# Logomatic.net
KiCad netlist of a schematic drawn in EAGLE
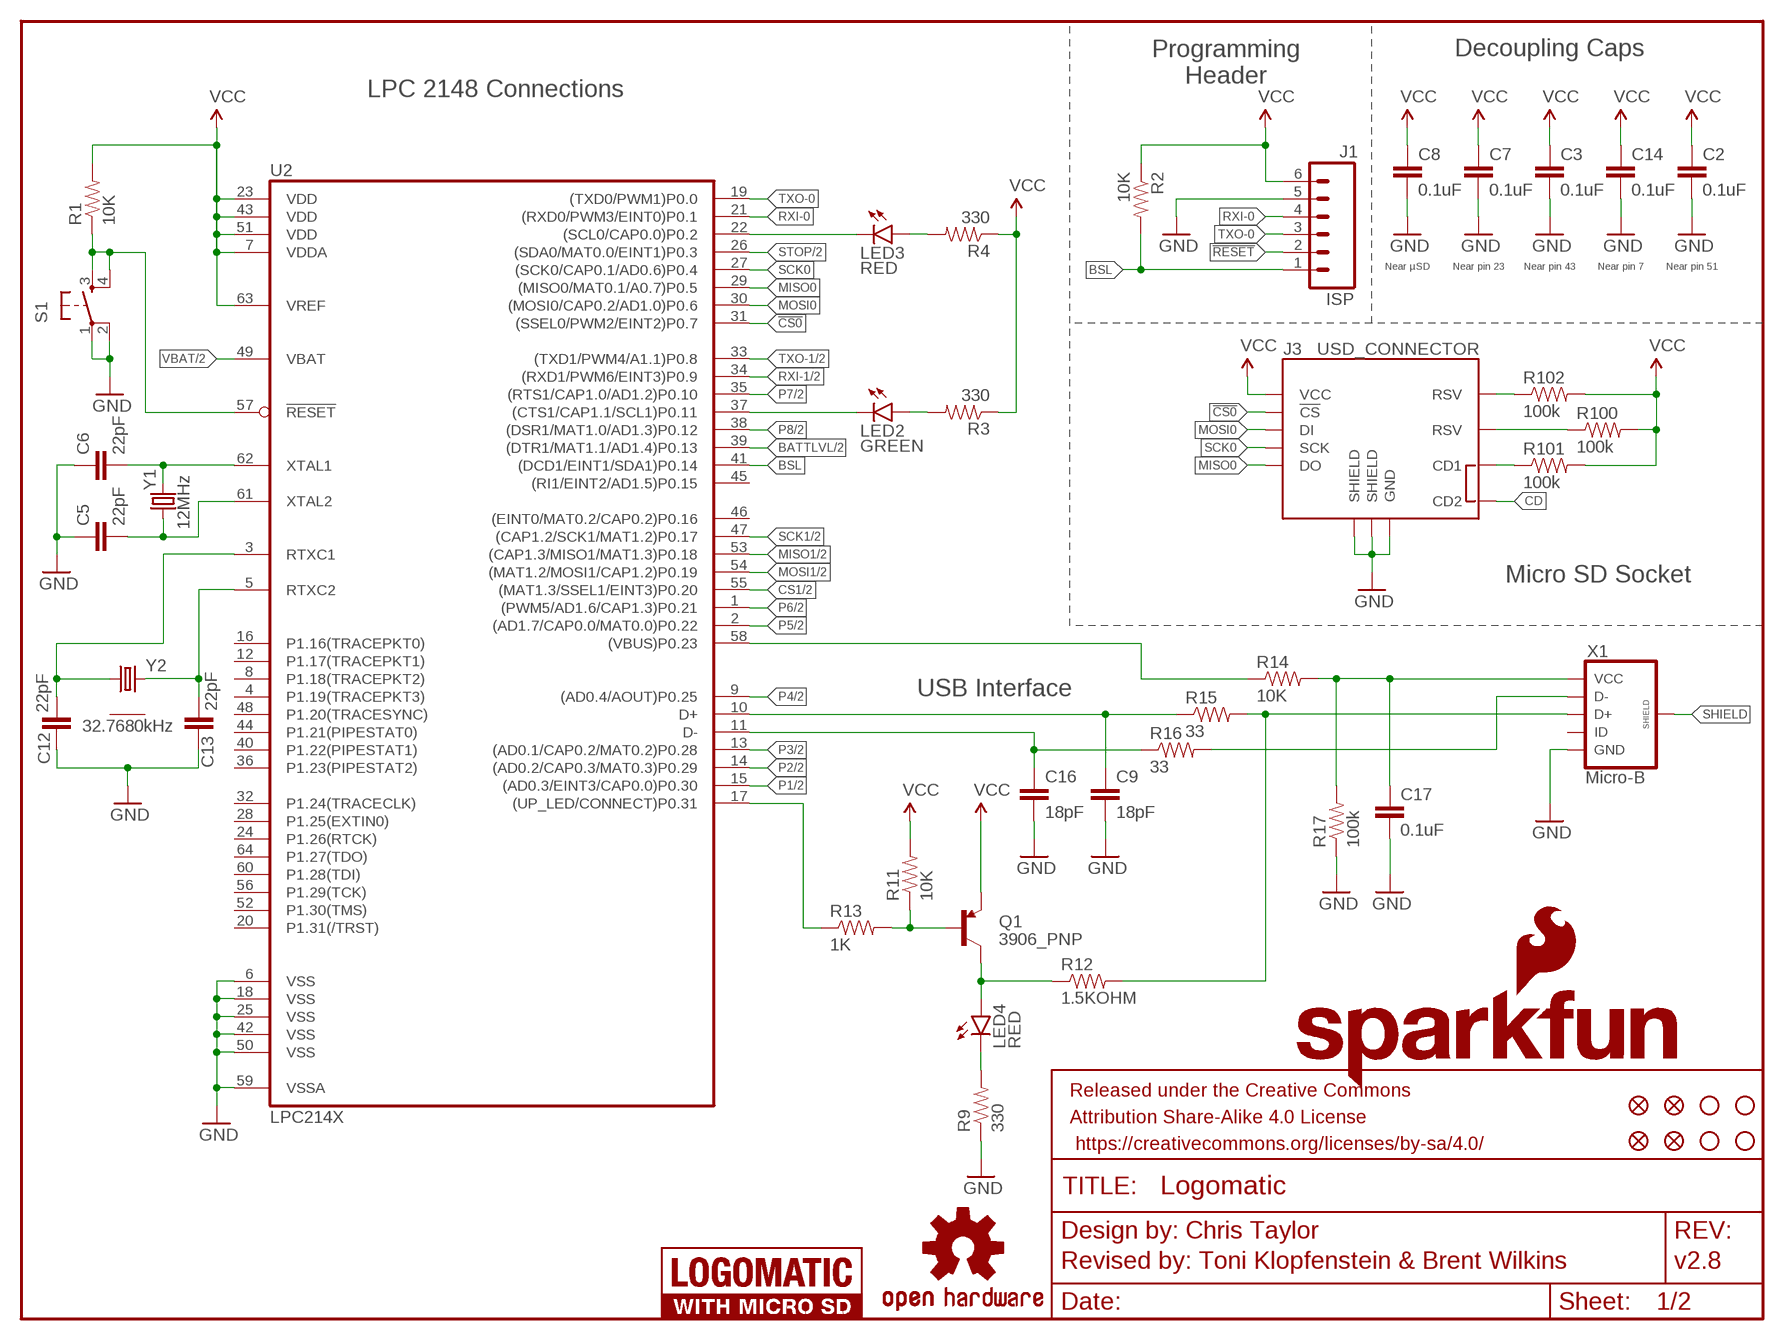
[diagram p0: schematic, sheet 1]
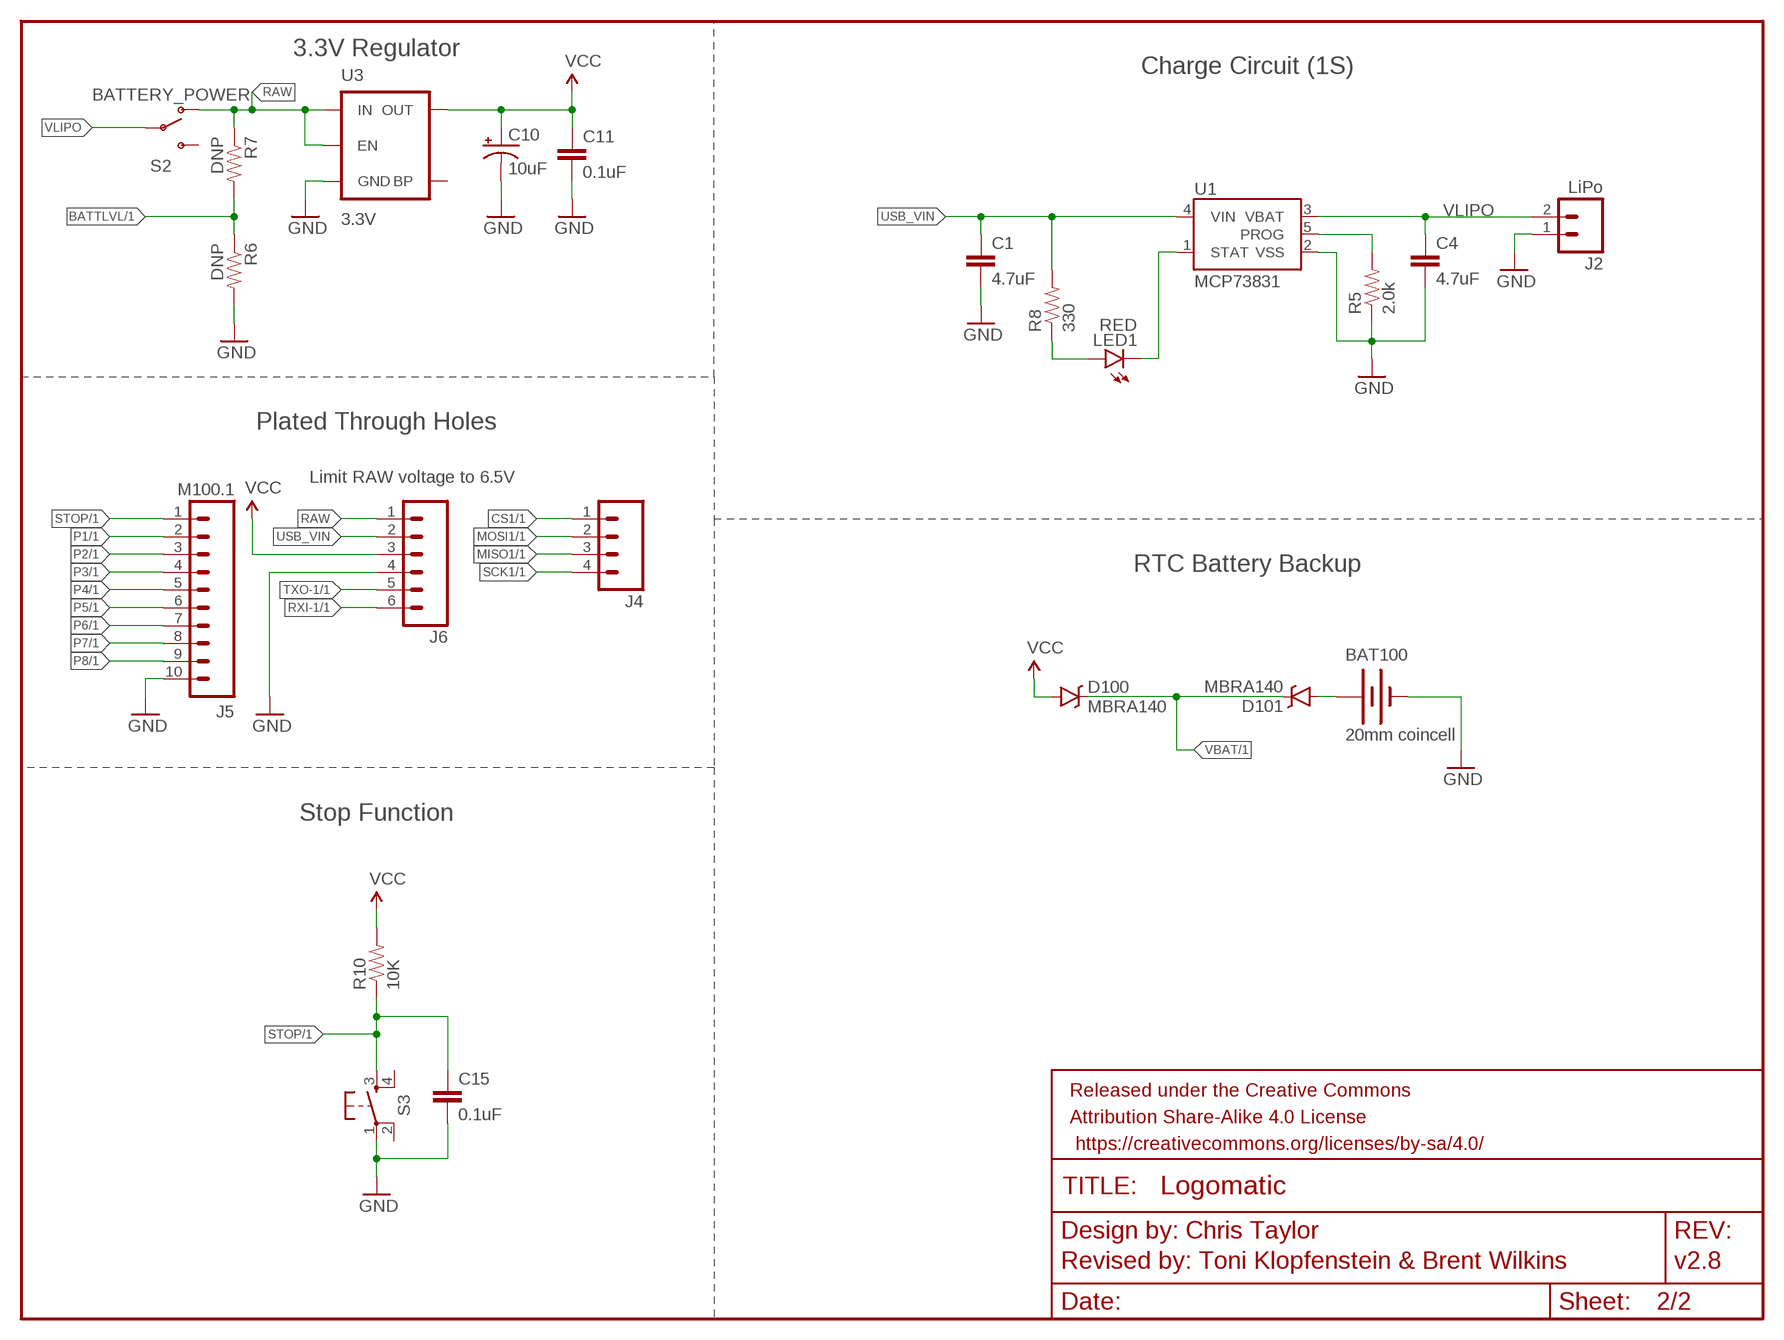
[diagram p1: schematic, sheet 2]

(export (version "E")
  (design (tool "Eeschema 10.0.6"))
  (components
    (comp (ref "BAT100")
      (value "20mm coincell")
      (footprint "eagle-import:BATTCON_20MM_4LEGS")
      (libsource (lib "eagle-import") (part "BATTERY20MM_4LEGS"))
    )
    (comp (ref "C1")
      (value "4.7uF")
      (footprint "eagle-import:0603-CAP")
      (libsource (lib "eagle-import") (part "4.7UF-6.3V-10%(0603)0603"))
    )
    (comp (ref "C4")
      (value "4.7uF")
      (footprint "eagle-import:0603-CAP")
      (libsource (lib "eagle-import") (part "4.7UF-6.3V-10%(0603)0603"))
    )
    (comp (ref "C10")
      (value "10uF")
      (footprint "eagle-import:EIA3216")
      (libsource (lib "eagle-import") (part "10UF-16V-10%(TANT)"))
    )
    (comp (ref "C11")
      (value "0.1uF")
      (footprint "eagle-import:0603-CAP")
      (libsource (lib "eagle-import") (part "0.1UF-25V(+80/-20%)(0603)"))
    )
    (comp (ref "C15")
      (value "0.1uF")
      (footprint "eagle-import:0603-CAP")
      (libsource (lib "eagle-import") (part "0.1UF-25V(+80/-20%)(0603)"))
    )
    (comp (ref "D100")
      (value "MBRA140")
      (footprint "eagle-import:SMA-DIODE")
      (libsource (lib "eagle-import") (part "MBRA140"))
    )
    (comp (ref "D101")
      (value "MBRA140")
      (footprint "eagle-import:SMA-DIODE")
      (libsource (lib "eagle-import") (part "MBRA140"))
    )
    (comp (ref "FRAME2")
      (value "FRAME-LETTERNO_PACKAGE")
      (footprint "eagle-import:DUMMY")
      (fields (field (name "DESIGNER") "Nobody"))
      (libsource (lib "eagle-import") (part "FRAME-LETTERNO_PACKAGE"))
    )
    (comp (ref "J2")
      (value "LiPo")
      (footprint "eagle-import:JST-2-SMD")
      (libsource (lib "eagle-import") (part "M02-JST-2MM-SMT"))
    )
    (comp (ref "J4")
      (value "M04PTH")
      (footprint "eagle-import:1X04")
      (libsource (lib "eagle-import") (part "M04PTH"))
    )
    (comp (ref "J5")
      (value "M100.1")
      (footprint "eagle-import:1X10")
      (libsource (lib "eagle-import") (part "M10SILK_FEMALE_PTH"))
    )
    (comp (ref "J6")
      (value "M06SILK_FEMALE_PTH")
      (footprint "eagle-import:1X06")
      (libsource (lib "eagle-import") (part "M06SILK_FEMALE_PTH"))
    )
    (comp (ref "LED1")
      (value "RED")
      (footprint "eagle-import:LED-0603")
      (libsource (lib "eagle-import") (part "LED-RED0603"))
    )
    (comp (ref "R5")
      (value "2.0k")
      (footprint "eagle-import:0603-RES")
      (libsource (lib "eagle-import") (part "2.0KOHM1/10W5%(0603)"))
    )
    (comp (ref "R6")
      (value "DNP")
      (footprint "eagle-import:0603-RES")
      (libsource (lib "eagle-import") (part "1MOHM-1/10W-1%(0603)"))
    )
    (comp (ref "R7")
      (value "DNP")
      (footprint "eagle-import:0603-RES")
      (libsource (lib "eagle-import") (part "1MOHM-1/10W-1%(0603)"))
    )
    (comp (ref "R8")
      (value "330")
      (footprint "eagle-import:0603-RES")
      (libsource (lib "eagle-import") (part "330OHM1/10W1%(0603)"))
    )
    (comp (ref "R10")
      (value "10K")
      (footprint "eagle-import:0603-RES")
      (libsource (lib "eagle-import") (part "10KOHM-1/10W-1%(0603)0603"))
    )
    (comp (ref "S2")
      (value "BATTERY_POWER")
      (footprint "eagle-import:AYZ0202")
      (libsource (lib "eagle-import") (part "SWITCH-SPDTSMD"))
    )
    (comp (ref "S3")
      (value "TAC_SWITCHSMD")
      (footprint "eagle-import:TACTILE-SWITCH-SMD")
      (libsource (lib "eagle-import") (part "TAC_SWITCHSMD"))
    )
    (comp (ref "U1")
      (value "MCP73831")
      (footprint "eagle-import:SOT23-5")
      (libsource (lib "eagle-import") (part "MCP73831"))
    )
    (comp (ref "U3")
      (value "3.3V")
      (footprint "eagle-import:SOT23-5")
      (libsource (lib "eagle-import") (part "MIC52053.3V"))
    )
    (comp (ref "C2")
      (value "0.1uF")
      (footprint "eagle-import:0603-CAP")
      (libsource (lib "eagle-import") (part "0.1UF-25V(+80/-20%)(0603)"))
    )
    (comp (ref "C3")
      (value "0.1uF")
      (footprint "eagle-import:0603-CAP")
      (libsource (lib "eagle-import") (part "0.1UF-25V(+80/-20%)(0603)"))
    )
    (comp (ref "C5")
      (value "22pF")
      (footprint "eagle-import:0603-CAP")
      (libsource (lib "eagle-import") (part "22PF-50V-5%(0603)"))
    )
    (comp (ref "C6")
      (value "22pF")
      (footprint "eagle-import:0603-CAP")
      (libsource (lib "eagle-import") (part "22PF-50V-5%(0603)"))
    )
    (comp (ref "C7")
      (value "0.1uF")
      (footprint "eagle-import:0603-CAP")
      (libsource (lib "eagle-import") (part "0.1UF-25V(+80/-20%)(0603)"))
    )
    (comp (ref "C8")
      (value "0.1uF")
      (footprint "eagle-import:0603-CAP")
      (libsource (lib "eagle-import") (part "0.1UF-25V(+80/-20%)(0603)"))
    )
    (comp (ref "C9")
      (value "18pF")
      (footprint "eagle-import:0603-CAP")
      (libsource (lib "eagle-import") (part "18PF-50V-5%(0603)"))
    )
    (comp (ref "C12")
      (value "22pF")
      (footprint "eagle-import:0603-CAP")
      (libsource (lib "eagle-import") (part "22PF-50V-5%(0603)"))
    )
    (comp (ref "C13")
      (value "22pF")
      (footprint "eagle-import:0603-CAP")
      (libsource (lib "eagle-import") (part "22PF-50V-5%(0603)"))
    )
    (comp (ref "C14")
      (value "0.1uF")
      (footprint "eagle-import:0603-CAP")
      (libsource (lib "eagle-import") (part "0.1UF-25V(+80/-20%)(0603)"))
    )
    (comp (ref "C16")
      (value "18pF")
      (footprint "eagle-import:0603-CAP")
      (libsource (lib "eagle-import") (part "18PF-50V-5%(0603)"))
    )
    (comp (ref "C17")
      (value "0.1uF")
      (footprint "eagle-import:0603-CAP")
      (libsource (lib "eagle-import") (part "0.1UF-25V(+80/-20%)(0603)"))
    )
    (comp (ref "FD1")
      (value "FIDUCIAL1X2")
      (footprint "eagle-import:FIDUCIAL-1X2")
      (libsource (lib "eagle-import") (part "FIDUCIAL1X2"))
    )
    (comp (ref "FD2")
      (value "FIDUCIAL1X2")
      (footprint "eagle-import:FIDUCIAL-1X2")
      (libsource (lib "eagle-import") (part "FIDUCIAL1X2"))
    )
    (comp (ref "FD100")
      (value "FIDUCIAL1X2")
      (footprint "eagle-import:FIDUCIAL-1X2")
      (libsource (lib "eagle-import") (part "FIDUCIAL1X2"))
    )
    (comp (ref "FD101")
      (value "FIDUCIAL1X2")
      (footprint "eagle-import:FIDUCIAL-1X2")
      (libsource (lib "eagle-import") (part "FIDUCIAL1X2"))
    )
    (comp (ref "FRAME1")
      (value "FRAME-LETTER")
      (footprint "eagle-import:CREATIVE_COMMONS")
      (libsource (lib "eagle-import") (part "FRAME-LETTER"))
    )
    (comp (ref "H1")
      (value "STAND-OFF")
      (footprint "eagle-import:STAND-OFF")
      (libsource (lib "eagle-import") (part "STAND-OFF"))
    )
    (comp (ref "H2")
      (value "STAND-OFF")
      (footprint "eagle-import:STAND-OFF")
      (libsource (lib "eagle-import") (part "STAND-OFF"))
    )
    (comp (ref "H3")
      (value "STAND-OFF")
      (footprint "eagle-import:STAND-OFF")
      (libsource (lib "eagle-import") (part "STAND-OFF"))
    )
    (comp (ref "H4")
      (value "STAND-OFF")
      (footprint "eagle-import:STAND-OFF")
      (libsource (lib "eagle-import") (part "STAND-OFF"))
    )
    (comp (ref "J1")
      (value "ISP")
      (footprint "eagle-import:1X06")
      (libsource (lib "eagle-import") (part "M06SILK_FEMALE_PTH"))
    )
    (comp (ref "J3")
      (value "USD_CONNECTOR")
      (footprint "eagle-import:MICRO-SD-SOCKET-PP")
      (libsource (lib "eagle-import") (part "USD_CONNECTOR"))
    )
    (comp (ref "LED2")
      (value "GREEN")
      (footprint "eagle-import:LED-0603")
      (libsource (lib "eagle-import") (part "LED-GREEN0603"))
    )
    (comp (ref "LED3")
      (value "RED")
      (footprint "eagle-import:LED-0603")
      (libsource (lib "eagle-import") (part "LED-RED0603"))
    )
    (comp (ref "LED4")
      (value "RED")
      (footprint "eagle-import:LED-0603")
      (libsource (lib "eagle-import") (part "LED-RED0603"))
    )
    (comp (ref "LOGO1")
      (value "SFE_LOGO_NAME.1_INCH")
      (footprint "eagle-import:SFE_LOGO_NAME_.1")
      (libsource (lib "eagle-import") (part "SFE_LOGO_NAME.1_INCH"))
    )
    (comp (ref "LOGO2")
      (value "SFE_LOGO_FLAME.1_INCH")
      (footprint "eagle-import:SFE_LOGO_FLAME_.1")
      (libsource (lib "eagle-import") (part "SFE_LOGO_FLAME.1_INCH"))
    )
    (comp (ref "LOGO100")
      (value "OSHW-LOGOL")
      (footprint "eagle-import:OSHW-LOGO-L")
      (libsource (lib "eagle-import") (part "OSHW-LOGOL"))
    )
    (comp (ref "LOGO101")
      (value "LOGOMATIC_LOGO")
      (footprint "eagle-import:LOGOMATIC_LOGO")
      (libsource (lib "eagle-import") (part "LOGOMATIC_LOGO"))
    )
    (comp (ref "Q1")
      (value "3906_PNP")
      (footprint "eagle-import:SOT23-3")
      (libsource (lib "eagle-import") (part "TRANSISTOR_PNPPMBT3906"))
    )
    (comp (ref "R1")
      (value "10K")
      (footprint "eagle-import:0603-RES")
      (libsource (lib "eagle-import") (part "10KOHM-1/10W-1%(0603)0603"))
    )
    (comp (ref "R2")
      (value "10K")
      (footprint "eagle-import:0603-RES")
      (libsource (lib "eagle-import") (part "10KOHM-1/10W-1%(0603)0603"))
    )
    (comp (ref "R3")
      (value "330")
      (footprint "eagle-import:0603-RES")
      (libsource (lib "eagle-import") (part "330OHM1/10W1%(0603)"))
    )
    (comp (ref "R4")
      (value "330")
      (footprint "eagle-import:0603-RES")
      (libsource (lib "eagle-import") (part "330OHM1/10W1%(0603)"))
    )
    (comp (ref "R9")
      (value "330")
      (footprint "eagle-import:0603-RES")
      (libsource (lib "eagle-import") (part "330OHM1/10W1%(0603)"))
    )
    (comp (ref "R11")
      (value "10K")
      (footprint "eagle-import:0603-RES")
      (libsource (lib "eagle-import") (part "10KOHM-1/10W-1%(0603)0603"))
    )
    (comp (ref "R12")
      (value "1.5KOHM")
      (footprint "eagle-import:0603")
      (libsource (lib "eagle-import") (part "1.5KOHM-1/10W-1%(0603)"))
    )
    (comp (ref "R13")
      (value "1K")
      (footprint "eagle-import:0603-RES")
      (libsource (lib "eagle-import") (part "1KOHM-1/10W-1%(0603)"))
    )
    (comp (ref "R14")
      (value "10K")
      (footprint "eagle-import:0603-RES")
      (libsource (lib "eagle-import") (part "10KOHM-1/10W-1%(0603)0603"))
    )
    (comp (ref "R15")
      (value "33")
      (footprint "eagle-import:0603-RES")
      (libsource (lib "eagle-import") (part "33OHM1/10W1%(0603)"))
    )
    (comp (ref "R16")
      (value "33")
      (footprint "eagle-import:0603-RES")
      (libsource (lib "eagle-import") (part "33OHM1/10W1%(0603)"))
    )
    (comp (ref "R17")
      (value "100k")
      (footprint "eagle-import:0603-RES")
      (libsource (lib "eagle-import") (part "100KOHM-1/10W-1%(0603)"))
    )
    (comp (ref "R100")
      (value "100k")
      (footprint "eagle-import:0603-RES")
      (libsource (lib "eagle-import") (part "100KOHM-1/10W-1%(0603)"))
    )
    (comp (ref "R101")
      (value "100k")
      (footprint "eagle-import:0603-RES")
      (libsource (lib "eagle-import") (part "100KOHM-1/10W-1%(0603)"))
    )
    (comp (ref "R102")
      (value "100k")
      (footprint "eagle-import:0603-RES")
      (libsource (lib "eagle-import") (part "100KOHM-1/10W-1%(0603)"))
    )
    (comp (ref "S1")
      (value "RESET")
      (footprint "eagle-import:TACTILE-SWITCH-SMD")
      (libsource (lib "eagle-import") (part "TAC_SWITCHSMD"))
    )
    (comp (ref "U2")
      (value "LPC214X")
      (footprint "eagle-import:LQFP-10X10-64")
      (libsource (lib "eagle-import") (part "LPC214X"))
    )
    (comp (ref "X1")
      (value "Micro-B")
      (footprint "eagle-import:USB-B-MICRO-SMD_V03")
      (libsource (lib "eagle-import") (part "USB_MICROB_PLUGCONN-11752"))
    )
    (comp (ref "Y1")
      (value "12MHz")
      (footprint "eagle-import:CRYSTAL-SMD-5X3")
      (libsource (lib "eagle-import") (part "CRYSTALCRYSTAL-SMD-5X3-12MHZ"))
    )
    (comp (ref "Y2")
      (value "32.7680kHz")
      (footprint "eagle-import:4-SOJ_5.5MM")
      (libsource (lib "eagle-import") (part "RTC_CRYSTAL32-SMD"))
    )
  )
  (nets
    (net (code "1") (name "BATTLVL") (class "Default")
      (node (ref "R6") (pin "1") (pinfunction "1_1") (pintype "passive"))
      (node (ref "R7") (pin "2") (pinfunction "2_2") (pintype "passive"))
      (node (ref "U2") (pin "39") (pinfunction "(DTR1/MAT1.1/AD1.4)P0.13_39") (pintype "bidirectional"))
    )
    (net (code "2") (name "BSL") (class "Default")
      (node (ref "J1") (pin "1") (pinfunction "1_1") (pintype "passive"))
      (node (ref "R2") (pin "2") (pinfunction "2_2") (pintype "passive"))
      (node (ref "U2") (pin "41") (pinfunction "(DCD1/EINT1/SDA1)P0.14_41") (pintype "bidirectional"))
    )
    (net (code "3") (name "CD") (class "Default")
      (node (ref "J3") (pin "CD2") (pinfunction "CD2_CD2") (pintype "bidirectional"))
    )
    (net (code "4") (name "CS1") (class "Default")
      (node (ref "J4") (pin "1") (pinfunction "1_1") (pintype "passive"))
      (node (ref "U2") (pin "55") (pinfunction "(MAT1.3/SSEL1/EINT3)P0.20_55") (pintype "bidirectional"))
    )
    (net (code "5") (name "GND") (class "Default")
      (node (ref "BAT100") (pin "NEGATIVE") (pinfunction "-_NEGATIVE") (pintype "power_in"))
      (node (ref "C1") (pin "2") (pinfunction "2_2") (pintype "passive"))
      (node (ref "C10") (pin "C") (pinfunction "-_C") (pintype "passive"))
      (node (ref "C11") (pin "2") (pinfunction "2_2") (pintype "passive"))
      (node (ref "C12") (pin "1") (pinfunction "1_1") (pintype "passive"))
      (node (ref "C13") (pin "1") (pinfunction "1_1") (pintype "passive"))
      (node (ref "C14") (pin "2") (pinfunction "2_2") (pintype "passive"))
      (node (ref "C15") (pin "2") (pinfunction "2_2") (pintype "passive"))
      (node (ref "C16") (pin "2") (pinfunction "2_2") (pintype "passive"))
      (node (ref "C17") (pin "2") (pinfunction "2_2") (pintype "passive"))
      (node (ref "C2") (pin "2") (pinfunction "2_2") (pintype "passive"))
      (node (ref "C3") (pin "2") (pinfunction "2_2") (pintype "passive"))
      (node (ref "C4") (pin "2") (pinfunction "2_2") (pintype "passive"))
      (node (ref "C5") (pin "1") (pinfunction "1_1") (pintype "passive"))
      (node (ref "C6") (pin "1") (pinfunction "1_1") (pintype "passive"))
      (node (ref "C7") (pin "2") (pinfunction "2_2") (pintype "passive"))
      (node (ref "C8") (pin "2") (pinfunction "2_2") (pintype "passive"))
      (node (ref "C9") (pin "2") (pinfunction "2_2") (pintype "passive"))
      (node (ref "J1") (pin "5") (pinfunction "5_5") (pintype "passive"))
      (node (ref "J2") (pin "1") (pinfunction "2_1") (pintype "passive"))
      (node (ref "J3") (pin "GND") (pinfunction "GND_GND") (pintype "bidirectional"))
      (node (ref "J3") (pin "GND1") (pinfunction "SHIELD_GND1") (pintype "bidirectional"))
      (node (ref "J3") (pin "GND3") (pinfunction "SHIELD_GND3") (pintype "bidirectional"))
      (node (ref "J5") (pin "10") (pinfunction "10_10") (pintype "passive"))
      (node (ref "J6") (pin "4") (pinfunction "4_4") (pintype "passive"))
      (node (ref "R17") (pin "1") (pinfunction "1_1") (pintype "passive"))
      (node (ref "R5") (pin "1") (pinfunction "1_1") (pintype "passive"))
      (node (ref "R6") (pin "2") (pinfunction "2_2") (pintype "passive"))
      (node (ref "R9") (pin "1") (pinfunction "1_1") (pintype "passive"))
      (node (ref "S1") (pin "1") (pinfunction "1_1") (pintype "passive"))
      (node (ref "S1") (pin "2") (pinfunction "2_2") (pintype "passive"))
      (node (ref "S3") (pin "1") (pinfunction "1_1") (pintype "passive"))
      (node (ref "U1") (pin "2") (pinfunction "VSS_2") (pintype "power_in"))
      (node (ref "U2") (pin "18") (pinfunction "VSS_18") (pintype "power_in"))
      (node (ref "U2") (pin "25") (pinfunction "VSS_25") (pintype "power_in"))
      (node (ref "U2") (pin "42") (pinfunction "VSS_42") (pintype "power_in"))
      (node (ref "U2") (pin "50") (pinfunction "VSS_50") (pintype "power_in"))
      (node (ref "U2") (pin "59") (pinfunction "VSSA_59") (pintype "power_in"))
      (node (ref "U2") (pin "6") (pinfunction "VSS_6") (pintype "power_in"))
      (node (ref "U3") (pin "2") (pinfunction "GND_2") (pintype "input"))
      (node (ref "X1") (pin "GND") (pinfunction "GND_GND") (pintype "bidirectional"))
    )
    (net (code "6") (name "MISO0") (class "Default")
      (node (ref "J3") (pin "DO") (pinfunction "DO_DO") (pintype "bidirectional"))
      (node (ref "U2") (pin "29") (pinfunction "(MISO0/MAT0.1/A0.7)P0.5_29") (pintype "bidirectional"))
    )
    (net (code "7") (name "MISO1") (class "Default")
      (node (ref "J4") (pin "3") (pinfunction "3_3") (pintype "passive"))
      (node (ref "U2") (pin "53") (pinfunction "(CAP1.3/MISO1/MAT1.3)P0.18_53") (pintype "bidirectional"))
    )
    (net (code "8") (name "MOSI0") (class "Default")
      (node (ref "J3") (pin "DI") (pinfunction "DI_DI") (pintype "bidirectional"))
      (node (ref "U2") (pin "30") (pinfunction "(MOSI0/CAP0.2/AD1.0)P0.6_30") (pintype "bidirectional"))
    )
    (net (code "9") (name "MOSI1") (class "Default")
      (node (ref "J4") (pin "2") (pinfunction "2_2") (pintype "passive"))
      (node (ref "U2") (pin "54") (pinfunction "(MAT1.2/MOSI1/CAP1.2)P0.19_54") (pintype "bidirectional"))
    )
    (net (code "10") (name "Net-(BAT100-+-PadPOSITIVE@1)") (class "Default")
      (node (ref "BAT100") (pin "POSITIVE@1") (pinfunction "+_POSITIVE@1") (pintype "power_in"))
      (node (ref "BAT100") (pin "POSITIVE@2") (pinfunction "+_POSITIVE@2") (pintype "power_in"))
      (node (ref "BAT100") (pin "POSITIVE@3") (pinfunction "+_POSITIVE@3") (pintype "power_in"))
      (node (ref "BAT100") (pin "POSITIVE@4") (pinfunction "+_POSITIVE@4") (pintype "power_in"))
      (node (ref "D101") (pin "A") (pinfunction "A_A") (pintype "passive"))
    )
    (net (code "11") (name "Net-(J3-PadCD1)") (class "Default")
      (node (ref "J3") (pin "CD1") (pinfunction "CD1_CD1") (pintype "bidirectional"))
      (node (ref "R101") (pin "1") (pinfunction "1_1") (pintype "passive"))
    )
    (net (code "12") (name "Net-(J3-RSV-PadRSV1)") (class "Default")
      (node (ref "J3") (pin "RSV1") (pinfunction "RSV_RSV1") (pintype "bidirectional"))
      (node (ref "R102") (pin "1") (pinfunction "1_1") (pintype "passive"))
    )
    (net (code "13") (name "Net-(J3-RSV-PadRSV2)") (class "Default")
      (node (ref "J3") (pin "RSV2") (pinfunction "RSV_RSV2") (pintype "bidirectional"))
      (node (ref "R100") (pin "1") (pinfunction "1_1") (pintype "passive"))
    )
    (net (code "14") (name "Net-(LED1-PadA)") (class "Default")
      (node (ref "LED1") (pin "A") (pinfunction "A_A") (pintype "passive"))
      (node (ref "R8") (pin "1") (pinfunction "1_1") (pintype "passive"))
    )
    (net (code "15") (name "Net-(LED2-PadA)") (class "Default")
      (node (ref "LED2") (pin "A") (pinfunction "A_A") (pintype "passive"))
      (node (ref "R3") (pin "2") (pinfunction "2_2") (pintype "passive"))
    )
    (net (code "16") (name "Net-(LED3-PadA)") (class "Default")
      (node (ref "LED3") (pin "A") (pinfunction "A_A") (pintype "passive"))
      (node (ref "R4") (pin "2") (pinfunction "2_2") (pintype "passive"))
    )
    (net (code "17") (name "Net-(LED4-PadC)") (class "Default")
      (node (ref "LED4") (pin "C") (pinfunction "C_C") (pintype "passive"))
      (node (ref "R9") (pin "2") (pinfunction "2_2") (pintype "passive"))
    )
    (net (code "18") (name "Net-(Q1-B)") (class "Default")
      (node (ref "Q1") (pin "1") (pinfunction "B_1") (pintype "passive"))
      (node (ref "R11") (pin "1") (pinfunction "1_1") (pintype "passive"))
      (node (ref "R13") (pin "2") (pinfunction "2_2") (pintype "passive"))
    )
    (net (code "19") (name "Net-(Q1-C)") (class "Default")
      (node (ref "LED4") (pin "A") (pinfunction "A_A") (pintype "passive"))
      (node (ref "Q1") (pin "3") (pinfunction "C_3") (pintype "passive"))
      (node (ref "R12") (pin "1") (pinfunction "1_1") (pintype "passive"))
    )
    (net (code "20") (name "Net-(R12-Pad2)") (class "Default")
      (node (ref "R12") (pin "2") (pinfunction "2_2") (pintype "passive"))
      (node (ref "R15") (pin "2") (pinfunction "2_2") (pintype "passive"))
      (node (ref "X1") (pin "D+") (pinfunction "D+_D+") (pintype "bidirectional"))
    )
    (net (code "21") (name "Net-(R16-Pad2)") (class "Default")
      (node (ref "R16") (pin "2") (pinfunction "2_2") (pintype "passive"))
      (node (ref "X1") (pin "D-") (pinfunction "D-_D-") (pintype "bidirectional"))
    )
    (net (code "22") (name "Net-(U1-PROG)") (class "Default")
      (node (ref "R5") (pin "2") (pinfunction "2_2") (pintype "passive"))
      (node (ref "U1") (pin "5") (pinfunction "PROG_5") (pintype "input"))
    )
    (net (code "23") (name "Net-(U1-STAT)") (class "Default")
      (node (ref "LED1") (pin "C") (pinfunction "C_C") (pintype "passive"))
      (node (ref "U1") (pin "1") (pinfunction "STAT_1") (pintype "output"))
    )
    (net (code "24") (name "Net-(U2-(CTS1{slash}CAP1.1{slash}SCL1)P0.11)") (class "Default")
      (node (ref "LED2") (pin "C") (pinfunction "C_C") (pintype "passive"))
      (node (ref "U2") (pin "37") (pinfunction "(CTS1/CAP1.1/SCL1)P0.11_37") (pintype "bidirectional"))
    )
    (net (code "25") (name "Net-(U2-(SCL0{slash}CAP0.0)P0.2)") (class "Default")
      (node (ref "LED3") (pin "C") (pinfunction "C_C") (pintype "passive"))
      (node (ref "U2") (pin "22") (pinfunction "(SCL0/CAP0.0)P0.2_22") (pintype "bidirectional"))
    )
    (net (code "26") (name "Net-(U2-(UP_LED{slash}CONNECT)P0.31)") (class "Default")
      (node (ref "R13") (pin "1") (pinfunction "1_1") (pintype "passive"))
      (node (ref "U2") (pin "17") (pinfunction "(UP_LED/CONNECT)P0.31_17") (pintype "bidirectional"))
    )
    (net (code "27") (name "Net-(U2-(VBUS)P0.23)") (class "Default")
      (node (ref "R14") (pin "1") (pinfunction "1_1") (pintype "passive"))
      (node (ref "U2") (pin "58") (pinfunction "(VBUS)P0.23_58") (pintype "bidirectional"))
    )
    (net (code "28") (name "Net-(U2-D+)") (class "Default")
      (node (ref "C9") (pin "1") (pinfunction "1_1") (pintype "passive"))
      (node (ref "R15") (pin "1") (pinfunction "1_1") (pintype "passive"))
      (node (ref "U2") (pin "10") (pinfunction "D+_10") (pintype "bidirectional"))
    )
    (net (code "29") (name "Net-(U2-D-)") (class "Default")
      (node (ref "C16") (pin "1") (pinfunction "1_1") (pintype "passive"))
      (node (ref "R16") (pin "1") (pinfunction "1_1") (pintype "passive"))
      (node (ref "U2") (pin "11") (pinfunction "D-_11") (pintype "bidirectional"))
    )
    (net (code "30") (name "Net-(U2-RTXC1)") (class "Default")
      (node (ref "C12") (pin "2") (pinfunction "2_2") (pintype "passive"))
      (node (ref "U2") (pin "3") (pinfunction "RTXC1_3") (pintype "input"))
      (node (ref "Y2") (pin "1") (pinfunction "1_1") (pintype "passive"))
    )
    (net (code "31") (name "Net-(U2-RTXC2)") (class "Default")
      (node (ref "C13") (pin "2") (pinfunction "2_2") (pintype "passive"))
      (node (ref "U2") (pin "5") (pinfunction "RTXC2_5") (pintype "output"))
      (node (ref "Y2") (pin "4") (pinfunction "4_4") (pintype "passive"))
    )
    (net (code "32") (name "Net-(U2-XTAL1)") (class "Default")
      (node (ref "C6") (pin "2") (pinfunction "2_2") (pintype "passive"))
      (node (ref "U2") (pin "62") (pinfunction "XTAL1_62") (pintype "input"))
      (node (ref "Y1") (pin "3") (pinfunction "2_3") (pintype "passive"))
    )
    (net (code "33") (name "Net-(U2-XTAL2)") (class "Default")
      (node (ref "C5") (pin "2") (pinfunction "2_2") (pintype "passive"))
      (node (ref "U2") (pin "61") (pinfunction "XTAL2_61") (pintype "output"))
      (node (ref "Y1") (pin "1") (pinfunction "1_1") (pintype "passive"))
    )
    (net (code "34") (name "P1") (class "Default")
      (node (ref "J5") (pin "2") (pinfunction "2_2") (pintype "passive"))
      (node (ref "U2") (pin "15") (pinfunction "(AD0.3/EINT3/CAP0.0)P0.30_15") (pintype "bidirectional"))
    )
    (net (code "35") (name "P2") (class "Default")
      (node (ref "J5") (pin "3") (pinfunction "3_3") (pintype "passive"))
      (node (ref "U2") (pin "14") (pinfunction "(AD0.2/CAP0.3/MAT0.3)P0.29_14") (pintype "bidirectional"))
    )
    (net (code "36") (name "P3") (class "Default")
      (node (ref "J5") (pin "4") (pinfunction "4_4") (pintype "passive"))
      (node (ref "U2") (pin "13") (pinfunction "(AD0.1/CAP0.2/MAT0.2)P0.28_13") (pintype "bidirectional"))
    )
    (net (code "37") (name "P4") (class "Default")
      (node (ref "J5") (pin "5") (pinfunction "5_5") (pintype "passive"))
      (node (ref "U2") (pin "9") (pinfunction "(AD0.4/AOUT)P0.25_9") (pintype "bidirectional"))
    )
    (net (code "38") (name "P5") (class "Default")
      (node (ref "J5") (pin "6") (pinfunction "6_6") (pintype "passive"))
      (node (ref "U2") (pin "2") (pinfunction "(AD1.7/CAP0.0/MAT0.0)P0.22_2") (pintype "bidirectional"))
    )
    (net (code "39") (name "P6") (class "Default")
      (node (ref "J5") (pin "7") (pinfunction "7_7") (pintype "passive"))
      (node (ref "U2") (pin "1") (pinfunction "(PWM5/AD1.6/CAP1.3)P0.21_1") (pintype "bidirectional"))
    )
    (net (code "40") (name "P7") (class "Default")
      (node (ref "J5") (pin "8") (pinfunction "8_8") (pintype "passive"))
      (node (ref "U2") (pin "35") (pinfunction "(RTS1/CAP1.0/AD1.2)P0.10_35") (pintype "bidirectional"))
    )
    (net (code "41") (name "P8") (class "Default")
      (node (ref "J5") (pin "9") (pinfunction "9_9") (pintype "passive"))
      (node (ref "U2") (pin "38") (pinfunction "(DSR1/MAT1.0/AD1.3)P0.12_38") (pintype "bidirectional"))
    )
    (net (code "42") (name "RAW") (class "Default")
      (node (ref "J6") (pin "1") (pinfunction "1_1") (pintype "passive"))
      (node (ref "R7") (pin "1") (pinfunction "1_1") (pintype "passive"))
      (node (ref "S2") (pin "1") (pinfunction "O_1") (pintype "passive"))
      (node (ref "U3") (pin "1") (pinfunction "IN_1") (pintype "input"))
      (node (ref "U3") (pin "3") (pinfunction "EN_3") (pintype "input"))
    )
    (net (code "43") (name "RXI-0") (class "Default")
      (node (ref "J1") (pin "4") (pinfunction "4_4") (pintype "passive"))
      (node (ref "U2") (pin "21") (pinfunction "(RXD0/PWM3/EINT0)P0.1_21") (pintype "bidirectional"))
    )
    (net (code "44") (name "RXI-1") (class "Default")
      (node (ref "J6") (pin "6") (pinfunction "6_6") (pintype "passive"))
      (node (ref "U2") (pin "34") (pinfunction "(RXD1/PWM6/EINT3)P0.9_34") (pintype "bidirectional"))
    )
    (net (code "45") (name "SCK0") (class "Default")
      (node (ref "J3") (pin "SCLK") (pinfunction "SCK_SCLK") (pintype "bidirectional"))
      (node (ref "U2") (pin "27") (pinfunction "(SCK0/CAP0.1/AD0.6)P0.4_27") (pintype "bidirectional"))
    )
    (net (code "46") (name "SCK1") (class "Default")
      (node (ref "J4") (pin "4") (pinfunction "4_4") (pintype "passive"))
      (node (ref "U2") (pin "47") (pinfunction "(CAP1.2/SCK1/MAT1.2)P0.17_47") (pintype "bidirectional"))
    )
    (net (code "47") (name "SHIELD") (class "Default")
      (node (ref "X1") (pin "SHIELD1") (pinfunction "SHIELD_SHIELD1") (pintype "bidirectional"))
      (node (ref "X1") (pin "SHIELD2") (pinfunction "SHIELD_SHIELD2") (pintype "bidirectional"))
      (node (ref "X1") (pin "SHIELD3") (pinfunction "SHIELD_SHIELD3") (pintype "bidirectional"))
    )
    (net (code "48") (name "STOP") (class "Default")
      (node (ref "C15") (pin "1") (pinfunction "1_1") (pintype "passive"))
      (node (ref "J5") (pin "1") (pinfunction "1_1") (pintype "passive"))
      (node (ref "R10") (pin "1") (pinfunction "1_1") (pintype "passive"))
      (node (ref "S3") (pin "3") (pinfunction "3_3") (pintype "passive"))
      (node (ref "U2") (pin "26") (pinfunction "(SDA0/MAT0.0/EINT1)P0.3_26") (pintype "bidirectional"))
    )
    (net (code "49") (name "TXO-0") (class "Default")
      (node (ref "J1") (pin "3") (pinfunction "3_3") (pintype "passive"))
      (node (ref "U2") (pin "19") (pinfunction "(TXD0/PWM1)P0.0_19") (pintype "bidirectional"))
    )
    (net (code "50") (name "TXO-1") (class "Default")
      (node (ref "J6") (pin "5") (pinfunction "5_5") (pintype "passive"))
      (node (ref "U2") (pin "33") (pinfunction "(TXD1/PWM4/A1.1)P0.8_33") (pintype "bidirectional"))
    )
    (net (code "51") (name "USB_VIN") (class "Default")
      (node (ref "C1") (pin "1") (pinfunction "1_1") (pintype "passive"))
      (node (ref "C17") (pin "1") (pinfunction "1_1") (pintype "passive"))
      (node (ref "J6") (pin "2") (pinfunction "2_2") (pintype "passive"))
      (node (ref "R14") (pin "2") (pinfunction "2_2") (pintype "passive"))
      (node (ref "R17") (pin "2") (pinfunction "2_2") (pintype "passive"))
      (node (ref "R8") (pin "2") (pinfunction "2_2") (pintype "passive"))
      (node (ref "U1") (pin "4") (pinfunction "VIN_4") (pintype "power_in"))
      (node (ref "X1") (pin "VBUS") (pinfunction "VCC_VBUS") (pintype "bidirectional"))
    )
    (net (code "52") (name "VBAT") (class "Default")
      (node (ref "D100") (pin "C") (pinfunction "C_C") (pintype "passive"))
      (node (ref "D101") (pin "C") (pinfunction "C_C") (pintype "passive"))
      (node (ref "U2") (pin "49") (pinfunction "VBAT_49") (pintype "power_in"))
    )
    (net (code "53") (name "VCC") (class "Default")
      (node (ref "C10") (pin "A") (pinfunction "+_A") (pintype "passive"))
      (node (ref "C11") (pin "1") (pinfunction "1_1") (pintype "passive"))
      (node (ref "C14") (pin "1") (pinfunction "1_1") (pintype "passive"))
      (node (ref "C2") (pin "1") (pinfunction "1_1") (pintype "passive"))
      (node (ref "C3") (pin "1") (pinfunction "1_1") (pintype "passive"))
      (node (ref "C7") (pin "1") (pinfunction "1_1") (pintype "passive"))
      (node (ref "C8") (pin "1") (pinfunction "1_1") (pintype "passive"))
      (node (ref "D100") (pin "A") (pinfunction "A_A") (pintype "passive"))
      (node (ref "J1") (pin "6") (pinfunction "6_6") (pintype "passive"))
      (node (ref "J3") (pin "VCC") (pinfunction "VCC_VCC") (pintype "bidirectional"))
      (node (ref "J6") (pin "3") (pinfunction "3_3") (pintype "passive"))
      (node (ref "Q1") (pin "2") (pinfunction "E_2") (pintype "passive"))
      (node (ref "R1") (pin "2") (pinfunction "2_2") (pintype "passive"))
      (node (ref "R10") (pin "2") (pinfunction "2_2") (pintype "passive"))
      (node (ref "R100") (pin "2") (pinfunction "2_2") (pintype "passive"))
      (node (ref "R101") (pin "2") (pinfunction "2_2") (pintype "passive"))
      (node (ref "R102") (pin "2") (pinfunction "2_2") (pintype "passive"))
      (node (ref "R11") (pin "2") (pinfunction "2_2") (pintype "passive"))
      (node (ref "R2") (pin "1") (pinfunction "1_1") (pintype "passive"))
      (node (ref "R3") (pin "1") (pinfunction "1_1") (pintype "passive"))
      (node (ref "R4") (pin "1") (pinfunction "1_1") (pintype "passive"))
      (node (ref "U2") (pin "23") (pinfunction "VDD_23") (pintype "power_in"))
      (node (ref "U2") (pin "43") (pinfunction "VDD_43") (pintype "power_in"))
      (node (ref "U2") (pin "51") (pinfunction "VDD_51") (pintype "power_in"))
      (node (ref "U2") (pin "63") (pinfunction "VREF_63") (pintype "input"))
      (node (ref "U2") (pin "7") (pinfunction "VDDA_7") (pintype "power_in"))
      (node (ref "U3") (pin "5") (pinfunction "OUT_5") (pintype "passive"))
    )
    (net (code "54") (name "VLIPO") (class "Default")
      (node (ref "C4") (pin "1") (pinfunction "1_1") (pintype "passive"))
      (node (ref "J2") (pin "2") (pinfunction "1_2") (pintype "passive"))
      (node (ref "S2") (pin "2") (pinfunction "P_2") (pintype "passive"))
      (node (ref "U1") (pin "3") (pinfunction "VBAT_3") (pintype "power_in"))
    )
    (net (code "55") (name "unconnected-(S2-S-Pad3)") (class "Default")
      (node (ref "S2") (pin "3") (pinfunction "S_3") (pintype "passive"))
    )
    (net (code "56") (name "unconnected-(S3-Pad2)") (class "Default")
      (node (ref "S3") (pin "2") (pinfunction "2_2") (pintype "passive"))
    )
    (net (code "57") (name "unconnected-(S3-Pad4)") (class "Default")
      (node (ref "S3") (pin "4") (pinfunction "4_4") (pintype "passive"))
    )
    (net (code "58") (name "unconnected-(U2-(EINT0{slash}MAT0.2{slash}CAP0.2)P0.16-Pad46)") (class "Default")
      (node (ref "U2") (pin "46") (pinfunction "(EINT0/MAT0.2/CAP0.2)P0.16_46") (pintype "bidirectional"))
    )
    (net (code "59") (name "unconnected-(U2-(RI1{slash}EINT2{slash}AD1.5)P0.15-Pad45)") (class "Default")
      (node (ref "U2") (pin "45") (pinfunction "(RI1/EINT2/AD1.5)P0.15_45") (pintype "bidirectional"))
    )
    (net (code "60") (name "unconnected-(U2-P1.16(TRACEPKT0)-Pad16)") (class "Default")
      (node (ref "U2") (pin "16") (pinfunction "P1.16(TRACEPKT0)_16") (pintype "bidirectional"))
    )
    (net (code "61") (name "unconnected-(U2-P1.17(TRACEPKT1)-Pad12)") (class "Default")
      (node (ref "U2") (pin "12") (pinfunction "P1.17(TRACEPKT1)_12") (pintype "bidirectional"))
    )
    (net (code "62") (name "unconnected-(U2-P1.18(TRACEPKT2)-Pad8)") (class "Default")
      (node (ref "U2") (pin "8") (pinfunction "P1.18(TRACEPKT2)_8") (pintype "bidirectional"))
    )
    (net (code "63") (name "unconnected-(U2-P1.19(TRACEPKT3)-Pad4)") (class "Default")
      (node (ref "U2") (pin "4") (pinfunction "P1.19(TRACEPKT3)_4") (pintype "bidirectional"))
    )
    (net (code "64") (name "unconnected-(U2-P1.20(TRACESYNC)-Pad48)") (class "Default")
      (node (ref "U2") (pin "48") (pinfunction "P1.20(TRACESYNC)_48") (pintype "bidirectional"))
    )
    (net (code "65") (name "unconnected-(U2-P1.21(PIPESTAT0)-Pad44)") (class "Default")
      (node (ref "U2") (pin "44") (pinfunction "P1.21(PIPESTAT0)_44") (pintype "bidirectional"))
    )
    (net (code "66") (name "unconnected-(U2-P1.22(PIPESTAT1)-Pad40)") (class "Default")
      (node (ref "U2") (pin "40") (pinfunction "P1.22(PIPESTAT1)_40") (pintype "bidirectional"))
    )
    (net (code "67") (name "unconnected-(U2-P1.23(PIPESTAT2)-Pad36)") (class "Default")
      (node (ref "U2") (pin "36") (pinfunction "P1.23(PIPESTAT2)_36") (pintype "bidirectional"))
    )
    (net (code "68") (name "unconnected-(U2-P1.24(TRACECLK)-Pad32)") (class "Default")
      (node (ref "U2") (pin "32") (pinfunction "P1.24(TRACECLK)_32") (pintype "bidirectional"))
    )
    (net (code "69") (name "unconnected-(U2-P1.25(EXTIN0)-Pad28)") (class "Default")
      (node (ref "U2") (pin "28") (pinfunction "P1.25(EXTIN0)_28") (pintype "bidirectional"))
    )
    (net (code "70") (name "unconnected-(U2-P1.26(RTCK)-Pad24)") (class "Default")
      (node (ref "U2") (pin "24") (pinfunction "P1.26(RTCK)_24") (pintype "bidirectional"))
    )
    (net (code "71") (name "unconnected-(U2-P1.27(TDO)-Pad64)") (class "Default")
      (node (ref "U2") (pin "64") (pinfunction "P1.27(TDO)_64") (pintype "bidirectional"))
    )
    (net (code "72") (name "unconnected-(U2-P1.28(TDI)-Pad60)") (class "Default")
      (node (ref "U2") (pin "60") (pinfunction "P1.28(TDI)_60") (pintype "bidirectional"))
    )
    (net (code "73") (name "unconnected-(U2-P1.29(TCK)-Pad56)") (class "Default")
      (node (ref "U2") (pin "56") (pinfunction "P1.29(TCK)_56") (pintype "bidirectional"))
    )
    (net (code "74") (name "unconnected-(U2-P1.30(TMS)-Pad52)") (class "Default")
      (node (ref "U2") (pin "52") (pinfunction "P1.30(TMS)_52") (pintype "bidirectional"))
    )
    (net (code "75") (name "unconnected-(U2-P1.31({slash}TRST)-Pad20)") (class "Default")
      (node (ref "U2") (pin "20") (pinfunction "P1.31(/TRST)_20") (pintype "bidirectional"))
    )
    (net (code "76") (name "unconnected-(U3-BP-Pad4)") (class "Default")
      (node (ref "U3") (pin "4") (pinfunction "BP_4") (pintype "input"))
    )
    (net (code "77") (name "unconnected-(X1-PadID)") (class "Default")
      (node (ref "X1") (pin "ID") (pinfunction "ID_ID") (pintype "bidirectional"))
    )
    (net (code "78") (name "unconnected-(Y2-Pad2)") (class "Default")
      (node (ref "Y2") (pin "2") (pinfunction "2_2") (pintype "passive"))
    )
    (net (code "79") (name "unconnected-(Y2-Pad3)") (class "Default")
      (node (ref "Y2") (pin "3") (pinfunction "3_3") (pintype "passive"))
    )
    (net (code "80") (name "~{CS0}") (class "Default")
      (node (ref "J3") (pin "CS") (pinfunction "~{CS}_CS") (pintype "bidirectional"))
      (node (ref "U2") (pin "31") (pinfunction "(SSEL0/PWM2/EINT2)P0.7_31") (pintype "bidirectional"))
    )
    (net (code "81") (name "~{RESET}") (class "Default")
      (node (ref "J1") (pin "2") (pinfunction "2_2") (pintype "passive"))
      (node (ref "R1") (pin "1") (pinfunction "1_1") (pintype "passive"))
      (node (ref "S1") (pin "3") (pinfunction "3_3") (pintype "passive"))
      (node (ref "S1") (pin "4") (pinfunction "4_4") (pintype "passive"))
      (node (ref "U2") (pin "57") (pinfunction "~{RESET}_57") (pintype "input"))
    )
  )
)
